# switch.net
KiCad netlist of a schematic drawn in EAGLE
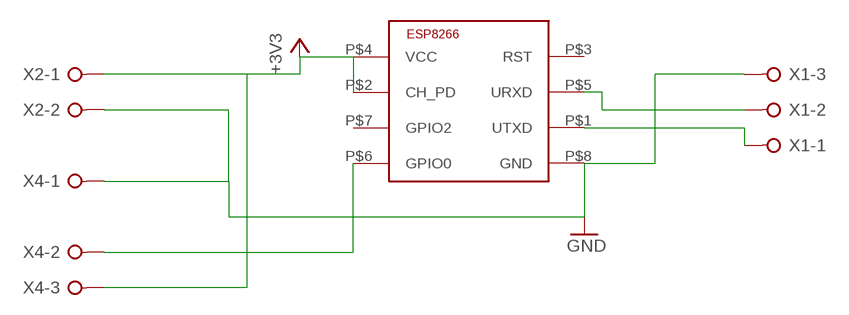
[diagram p0: schematic, sheet 1]

(export (version "E")
  (design (tool "Eeschema 10.0.6"))
  (components
    (comp (ref "U$1")
      (value "ESP8266-01")
      (footprint "eagle-import:ESP-01")
      (libsource (lib "eagle-import") (part "ESP8266-01"))
    )
    (comp (ref "X1")
      (value "W237-3E")
      (footprint "eagle-import:W237-3E")
      (libsource (lib "eagle-import") (part "W237-3E"))
    )
    (comp (ref "X2")
      (value "W237-02P")
      (footprint "eagle-import:W237-132")
      (libsource (lib "eagle-import") (part "W237-02P"))
    )
    (comp (ref "X4")
      (value "W237-3E")
      (footprint "eagle-import:W237-3E")
      (libsource (lib "eagle-import") (part "W237-3E"))
    )
  )
  (nets
    (net (code "1") (name "+3V3") (class "Default")
      (node (ref "U$1") (pin "P$2") (pinfunction "CH_PD_P$2") (pintype "bidirectional"))
      (node (ref "U$1") (pin "P$4") (pinfunction "VCC_P$4") (pintype "bidirectional"))
      (node (ref "X2") (pin "1") (pinfunction "KL_1") (pintype "passive"))
      (node (ref "X4") (pin "3") (pinfunction "KL_3") (pintype "passive"))
    )
    (net (code "2") (name "GND") (class "Default")
      (node (ref "U$1") (pin "P$8") (pinfunction "GND_P$8") (pintype "bidirectional"))
      (node (ref "X1") (pin "3") (pinfunction "KL_3") (pintype "passive"))
      (node (ref "X2") (pin "2") (pinfunction "KL_2") (pintype "passive"))
      (node (ref "X4") (pin "1") (pinfunction "KL_1") (pintype "passive"))
    )
    (net (code "3") (name "Net-(U$1-GPIO0)") (class "Default")
      (node (ref "U$1") (pin "P$6") (pinfunction "GPIO0_P$6") (pintype "bidirectional"))
      (node (ref "X4") (pin "2") (pinfunction "KL_2") (pintype "passive"))
    )
    (net (code "4") (name "Net-(U$1-URXD)") (class "Default")
      (node (ref "U$1") (pin "P$5") (pinfunction "URXD_P$5") (pintype "bidirectional"))
      (node (ref "X1") (pin "2") (pinfunction "KL_2") (pintype "passive"))
    )
    (net (code "5") (name "Net-(U$1-UTXD)") (class "Default")
      (node (ref "U$1") (pin "P$1") (pinfunction "UTXD_P$1") (pintype "bidirectional"))
      (node (ref "X1") (pin "1") (pinfunction "KL_1") (pintype "passive"))
    )
    (net (code "6") (name "unconnected-(U$1-GPIO2-PadP$7)") (class "Default")
      (node (ref "U$1") (pin "P$7") (pinfunction "GPIO2_P$7") (pintype "bidirectional"))
    )
    (net (code "7") (name "unconnected-(U$1-RST-PadP$3)") (class "Default")
      (node (ref "U$1") (pin "P$3") (pinfunction "RST_P$3") (pintype "bidirectional"))
    )
  )
)
